# Backpowering_Circuit.net
KiCad netlist of a schematic drawn in EAGLE
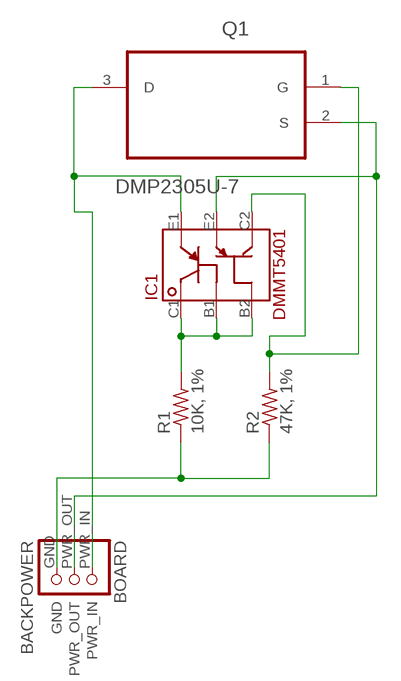
[diagram p0: schematic, sheet 1]

(export (version "E")
  (design (tool "Eeschema 10.0.6"))
  (components
    (comp (ref "BOARD")
      (value "BACKPOWER")
      (footprint "eagle-import:BACKPOWER")
      (libsource (lib "eagle-import") (part "BACKPOWER"))
    )
    (comp (ref "IC1")
      (value "DMMT5401")
      (footprint "eagle-import:DMMT5401")
      (libsource (lib "eagle-import") (part "DMMT5401DMMT"))
    )
    (comp (ref "Q1")
      (value "DMP2305U-7")
      (footprint "eagle-import:SOT103P240X110-3N")
      (libsource (lib "eagle-import") (part "DMP2305U-7"))
    )
    (comp (ref "R1")
      (value "10K, 1%")
      (footprint "eagle-import:R1005")
      (libsource (lib "eagle-import") (part "R-US_R1005"))
    )
    (comp (ref "R2")
      (value "47K, 1%")
      (footprint "eagle-import:R1005")
      (libsource (lib "eagle-import") (part "R-US_R1005"))
    )
  )
  (nets
    (net (code "1") (name "Net-(BOARD-PadGND)") (class "Default")
      (node (ref "BOARD") (pin "GND") (pinfunction "GND_GND") (pintype "power_in"))
      (node (ref "R1") (pin "1") (pinfunction "1_1") (pintype "passive"))
      (node (ref "R2") (pin "1") (pinfunction "1_1") (pintype "passive"))
    )
    (net (code "2") (name "Net-(IC1-PadB1)") (class "Default")
      (node (ref "IC1") (pin "B1") (pinfunction "B1_B1") (pintype "bidirectional"))
      (node (ref "IC1") (pin "B2") (pinfunction "B2_B2") (pintype "bidirectional"))
      (node (ref "IC1") (pin "C1") (pinfunction "C1_C1") (pintype "bidirectional"))
      (node (ref "R1") (pin "2") (pinfunction "2_2") (pintype "passive"))
    )
    (net (code "3") (name "Net-(Q1-D)") (class "Default")
      (node (ref "BOARD") (pin "PWR_IN") (pinfunction "PWR_IN_PWR_IN") (pintype "power_in"))
      (node (ref "IC1") (pin "E1") (pinfunction "E1_E1") (pintype "bidirectional"))
      (node (ref "Q1") (pin "3") (pinfunction "D_3") (pintype "output"))
    )
    (net (code "4") (name "Net-(Q1-G)") (class "Default")
      (node (ref "IC1") (pin "C2") (pinfunction "C2_C2") (pintype "bidirectional"))
      (node (ref "Q1") (pin "1") (pinfunction "G_1") (pintype "input"))
      (node (ref "R2") (pin "2") (pinfunction "2_2") (pintype "passive"))
    )
    (net (code "5") (name "Net-(Q1-S)") (class "Default")
      (node (ref "BOARD") (pin "PWR_OUT") (pinfunction "PWR_OUT_PWR_OUT") (pintype "power_in"))
      (node (ref "IC1") (pin "E2") (pinfunction "E2_E2") (pintype "bidirectional"))
      (node (ref "Q1") (pin "2") (pinfunction "S_2") (pintype "passive"))
    )
  )
)
